# untitled2.net
KiCad netlist of a schematic drawn in EAGLE
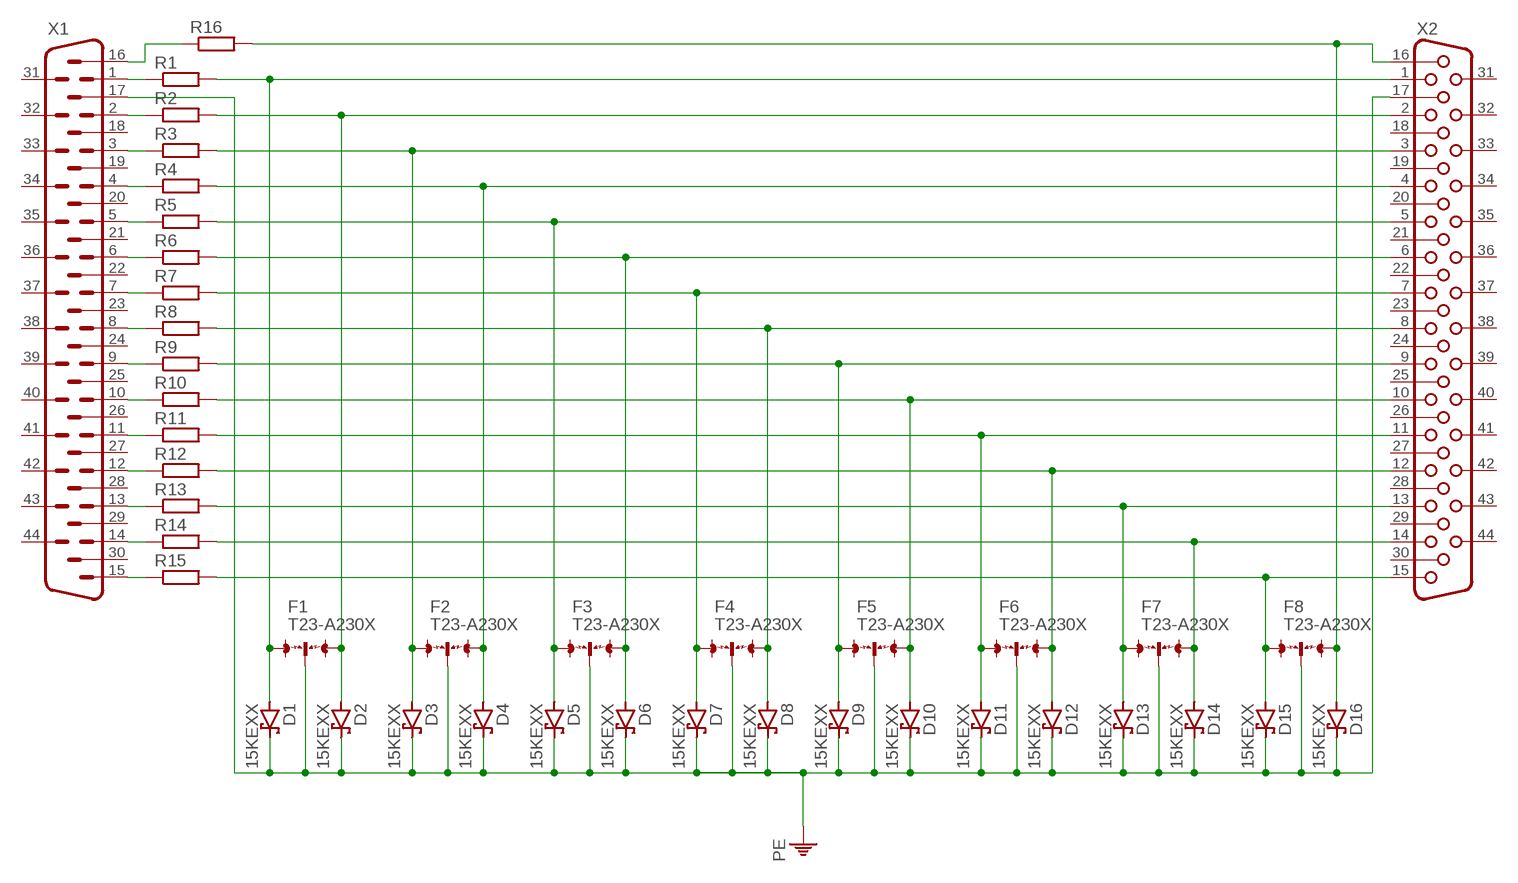
[diagram p0: schematic, sheet 1]

(export (version "E")
  (design (tool "Eeschema 10.0.6"))
  (components
    (comp (ref "D1")
      (value "15KEXX")
      (footprint "eagle-import:CB429-17")
      (libsource (lib "eagle-import") (part "15KEXX"))
    )
    (comp (ref "D2")
      (value "15KEXX")
      (footprint "eagle-import:CB429-17")
      (libsource (lib "eagle-import") (part "15KEXX"))
    )
    (comp (ref "D3")
      (value "15KEXX")
      (footprint "eagle-import:CB429-17")
      (libsource (lib "eagle-import") (part "15KEXX"))
    )
    (comp (ref "D4")
      (value "15KEXX")
      (footprint "eagle-import:CB429-17")
      (libsource (lib "eagle-import") (part "15KEXX"))
    )
    (comp (ref "D5")
      (value "15KEXX")
      (footprint "eagle-import:CB429-17")
      (libsource (lib "eagle-import") (part "15KEXX"))
    )
    (comp (ref "D6")
      (value "15KEXX")
      (footprint "eagle-import:CB429-17")
      (libsource (lib "eagle-import") (part "15KEXX"))
    )
    (comp (ref "D7")
      (value "15KEXX")
      (footprint "eagle-import:CB429-17")
      (libsource (lib "eagle-import") (part "15KEXX"))
    )
    (comp (ref "D8")
      (value "15KEXX")
      (footprint "eagle-import:CB429-17")
      (libsource (lib "eagle-import") (part "15KEXX"))
    )
    (comp (ref "D9")
      (value "15KEXX")
      (footprint "eagle-import:CB429-17")
      (libsource (lib "eagle-import") (part "15KEXX"))
    )
    (comp (ref "D10")
      (value "15KEXX")
      (footprint "eagle-import:CB429-17")
      (libsource (lib "eagle-import") (part "15KEXX"))
    )
    (comp (ref "D11")
      (value "15KEXX")
      (footprint "eagle-import:CB429-17")
      (libsource (lib "eagle-import") (part "15KEXX"))
    )
    (comp (ref "D12")
      (value "15KEXX")
      (footprint "eagle-import:CB429-17")
      (libsource (lib "eagle-import") (part "15KEXX"))
    )
    (comp (ref "D13")
      (value "15KEXX")
      (footprint "eagle-import:CB429-17")
      (libsource (lib "eagle-import") (part "15KEXX"))
    )
    (comp (ref "D14")
      (value "15KEXX")
      (footprint "eagle-import:CB429-17")
      (libsource (lib "eagle-import") (part "15KEXX"))
    )
    (comp (ref "D15")
      (value "15KEXX")
      (footprint "eagle-import:CB429-17")
      (libsource (lib "eagle-import") (part "15KEXX"))
    )
    (comp (ref "D16")
      (value "15KEXX")
      (footprint "eagle-import:CB429-17")
      (libsource (lib "eagle-import") (part "15KEXX"))
    )
    (comp (ref "F1")
      (value "T23-A230X")
      (footprint "eagle-import:T23-A230X")
      (libsource (lib "eagle-import") (part "T23-A230X"))
    )
    (comp (ref "F2")
      (value "T23-A230X")
      (footprint "eagle-import:T23-A230X")
      (libsource (lib "eagle-import") (part "T23-A230X"))
    )
    (comp (ref "F3")
      (value "T23-A230X")
      (footprint "eagle-import:T23-A230X")
      (libsource (lib "eagle-import") (part "T23-A230X"))
    )
    (comp (ref "F4")
      (value "T23-A230X")
      (footprint "eagle-import:T23-A230X")
      (libsource (lib "eagle-import") (part "T23-A230X"))
    )
    (comp (ref "F5")
      (value "T23-A230X")
      (footprint "eagle-import:T23-A230X")
      (libsource (lib "eagle-import") (part "T23-A230X"))
    )
    (comp (ref "F6")
      (value "T23-A230X")
      (footprint "eagle-import:T23-A230X")
      (libsource (lib "eagle-import") (part "T23-A230X"))
    )
    (comp (ref "F7")
      (value "T23-A230X")
      (footprint "eagle-import:T23-A230X")
      (libsource (lib "eagle-import") (part "T23-A230X"))
    )
    (comp (ref "F8")
      (value "T23-A230X")
      (footprint "eagle-import:T23-A230X")
      (libsource (lib "eagle-import") (part "T23-A230X"))
    )
    (comp (ref "R1")
      (value "R-EU_R1210")
      (footprint "eagle-import:R1210")
      (libsource (lib "eagle-import") (part "R-EU_R1210"))
    )
    (comp (ref "R2")
      (value "R-EU_R1210")
      (footprint "eagle-import:R1210")
      (libsource (lib "eagle-import") (part "R-EU_R1210"))
    )
    (comp (ref "R3")
      (value "R-EU_R1210")
      (footprint "eagle-import:R1210")
      (libsource (lib "eagle-import") (part "R-EU_R1210"))
    )
    (comp (ref "R4")
      (value "R-EU_R1210")
      (footprint "eagle-import:R1210")
      (libsource (lib "eagle-import") (part "R-EU_R1210"))
    )
    (comp (ref "R5")
      (value "R-EU_R1210")
      (footprint "eagle-import:R1210")
      (libsource (lib "eagle-import") (part "R-EU_R1210"))
    )
    (comp (ref "R6")
      (value "R-EU_R1210")
      (footprint "eagle-import:R1210")
      (libsource (lib "eagle-import") (part "R-EU_R1210"))
    )
    (comp (ref "R7")
      (value "R-EU_R1210")
      (footprint "eagle-import:R1210")
      (libsource (lib "eagle-import") (part "R-EU_R1210"))
    )
    (comp (ref "R8")
      (value "R-EU_R1210")
      (footprint "eagle-import:R1210")
      (libsource (lib "eagle-import") (part "R-EU_R1210"))
    )
    (comp (ref "R9")
      (value "R-EU_R1210")
      (footprint "eagle-import:R1210")
      (libsource (lib "eagle-import") (part "R-EU_R1210"))
    )
    (comp (ref "R10")
      (value "R-EU_R1210")
      (footprint "eagle-import:R1210")
      (libsource (lib "eagle-import") (part "R-EU_R1210"))
    )
    (comp (ref "R11")
      (value "R-EU_R1210")
      (footprint "eagle-import:R1210")
      (libsource (lib "eagle-import") (part "R-EU_R1210"))
    )
    (comp (ref "R12")
      (value "R-EU_R1210")
      (footprint "eagle-import:R1210")
      (libsource (lib "eagle-import") (part "R-EU_R1210"))
    )
    (comp (ref "R13")
      (value "R-EU_R1210")
      (footprint "eagle-import:R1210")
      (libsource (lib "eagle-import") (part "R-EU_R1210"))
    )
    (comp (ref "R14")
      (value "R-EU_R1210")
      (footprint "eagle-import:R1210")
      (libsource (lib "eagle-import") (part "R-EU_R1210"))
    )
    (comp (ref "R15")
      (value "R-EU_R1210")
      (footprint "eagle-import:R1210")
      (libsource (lib "eagle-import") (part "R-EU_R1210"))
    )
    (comp (ref "R16")
      (value "R-EU_R1210")
      (footprint "eagle-import:R1210")
      (libsource (lib "eagle-import") (part "R-EU_R1210"))
    )
    (comp (ref "X1")
      (value "HM44H")
      (footprint "eagle-import:HDM44H")
      (libsource (lib "eagle-import") (part "HM44H"))
    )
    (comp (ref "X2")
      (value "HF44H")
      (footprint "eagle-import:HDF44H")
      (libsource (lib "eagle-import") (part "HF44H"))
    )
  )
  (nets
    (net (code "1") (name "Net-(D1-PadA)") (class "Default")
      (node (ref "D1") (pin "A") (pinfunction "A_A") (pintype "passive"))
      (node (ref "F1") (pin "1") (pinfunction "1_1") (pintype "passive"))
      (node (ref "R1") (pin "2") (pinfunction "2_2") (pintype "passive"))
      (node (ref "X2") (pin "1") (pinfunction "1_1") (pintype "passive"))
    )
    (net (code "2") (name "Net-(D2-PadA)") (class "Default")
      (node (ref "D2") (pin "A") (pinfunction "A_A") (pintype "passive"))
      (node (ref "F1") (pin "3") (pinfunction "3_3") (pintype "passive"))
      (node (ref "R2") (pin "2") (pinfunction "2_2") (pintype "passive"))
      (node (ref "X2") (pin "2") (pinfunction "2_2") (pintype "passive"))
    )
    (net (code "3") (name "Net-(D3-PadA)") (class "Default")
      (node (ref "D3") (pin "A") (pinfunction "A_A") (pintype "passive"))
      (node (ref "F2") (pin "1") (pinfunction "1_1") (pintype "passive"))
      (node (ref "R3") (pin "2") (pinfunction "2_2") (pintype "passive"))
      (node (ref "X2") (pin "3") (pinfunction "3_3") (pintype "passive"))
    )
    (net (code "4") (name "Net-(D4-PadA)") (class "Default")
      (node (ref "D4") (pin "A") (pinfunction "A_A") (pintype "passive"))
      (node (ref "F2") (pin "3") (pinfunction "3_3") (pintype "passive"))
      (node (ref "R4") (pin "2") (pinfunction "2_2") (pintype "passive"))
      (node (ref "X2") (pin "4") (pinfunction "4_4") (pintype "passive"))
    )
    (net (code "5") (name "Net-(D5-PadA)") (class "Default")
      (node (ref "D5") (pin "A") (pinfunction "A_A") (pintype "passive"))
      (node (ref "F3") (pin "1") (pinfunction "1_1") (pintype "passive"))
      (node (ref "R5") (pin "2") (pinfunction "2_2") (pintype "passive"))
      (node (ref "X2") (pin "5") (pinfunction "5_5") (pintype "passive"))
    )
    (net (code "6") (name "Net-(D6-PadA)") (class "Default")
      (node (ref "D6") (pin "A") (pinfunction "A_A") (pintype "passive"))
      (node (ref "F3") (pin "3") (pinfunction "3_3") (pintype "passive"))
      (node (ref "R6") (pin "2") (pinfunction "2_2") (pintype "passive"))
      (node (ref "X2") (pin "6") (pinfunction "6_6") (pintype "passive"))
    )
    (net (code "7") (name "Net-(D7-PadA)") (class "Default")
      (node (ref "D7") (pin "A") (pinfunction "A_A") (pintype "passive"))
      (node (ref "F4") (pin "1") (pinfunction "1_1") (pintype "passive"))
      (node (ref "R7") (pin "2") (pinfunction "2_2") (pintype "passive"))
      (node (ref "X2") (pin "7") (pinfunction "7_7") (pintype "passive"))
    )
    (net (code "8") (name "Net-(D8-PadA)") (class "Default")
      (node (ref "D8") (pin "A") (pinfunction "A_A") (pintype "passive"))
      (node (ref "F4") (pin "3") (pinfunction "3_3") (pintype "passive"))
      (node (ref "R8") (pin "2") (pinfunction "2_2") (pintype "passive"))
      (node (ref "X2") (pin "8") (pinfunction "8_8") (pintype "passive"))
    )
    (net (code "9") (name "Net-(D9-PadA)") (class "Default")
      (node (ref "D9") (pin "A") (pinfunction "A_A") (pintype "passive"))
      (node (ref "F5") (pin "1") (pinfunction "1_1") (pintype "passive"))
      (node (ref "R9") (pin "2") (pinfunction "2_2") (pintype "passive"))
      (node (ref "X2") (pin "9") (pinfunction "9_9") (pintype "passive"))
    )
    (net (code "10") (name "Net-(D10-PadA)") (class "Default")
      (node (ref "D10") (pin "A") (pinfunction "A_A") (pintype "passive"))
      (node (ref "F5") (pin "3") (pinfunction "3_3") (pintype "passive"))
      (node (ref "R10") (pin "2") (pinfunction "2_2") (pintype "passive"))
      (node (ref "X2") (pin "10") (pinfunction "10_10") (pintype "passive"))
    )
    (net (code "11") (name "Net-(D11-PadA)") (class "Default")
      (node (ref "D11") (pin "A") (pinfunction "A_A") (pintype "passive"))
      (node (ref "F6") (pin "1") (pinfunction "1_1") (pintype "passive"))
      (node (ref "R11") (pin "2") (pinfunction "2_2") (pintype "passive"))
      (node (ref "X2") (pin "11") (pinfunction "11_11") (pintype "passive"))
    )
    (net (code "12") (name "Net-(D12-PadA)") (class "Default")
      (node (ref "D12") (pin "A") (pinfunction "A_A") (pintype "passive"))
      (node (ref "F6") (pin "3") (pinfunction "3_3") (pintype "passive"))
      (node (ref "R12") (pin "2") (pinfunction "2_2") (pintype "passive"))
      (node (ref "X2") (pin "12") (pinfunction "12_12") (pintype "passive"))
    )
    (net (code "13") (name "Net-(D13-PadA)") (class "Default")
      (node (ref "D13") (pin "A") (pinfunction "A_A") (pintype "passive"))
      (node (ref "F7") (pin "1") (pinfunction "1_1") (pintype "passive"))
      (node (ref "R13") (pin "2") (pinfunction "2_2") (pintype "passive"))
      (node (ref "X2") (pin "13") (pinfunction "13_13") (pintype "passive"))
    )
    (net (code "14") (name "Net-(D14-PadA)") (class "Default")
      (node (ref "D14") (pin "A") (pinfunction "A_A") (pintype "passive"))
      (node (ref "F7") (pin "3") (pinfunction "3_3") (pintype "passive"))
      (node (ref "R14") (pin "2") (pinfunction "2_2") (pintype "passive"))
      (node (ref "X2") (pin "14") (pinfunction "14_14") (pintype "passive"))
    )
    (net (code "15") (name "Net-(D15-PadA)") (class "Default")
      (node (ref "D15") (pin "A") (pinfunction "A_A") (pintype "passive"))
      (node (ref "F8") (pin "1") (pinfunction "1_1") (pintype "passive"))
      (node (ref "R15") (pin "2") (pinfunction "2_2") (pintype "passive"))
      (node (ref "X2") (pin "15") (pinfunction "15_15") (pintype "passive"))
    )
    (net (code "16") (name "Net-(D16-PadA)") (class "Default")
      (node (ref "D16") (pin "A") (pinfunction "A_A") (pintype "passive"))
      (node (ref "F8") (pin "3") (pinfunction "3_3") (pintype "passive"))
      (node (ref "R16") (pin "2") (pinfunction "2_2") (pintype "passive"))
      (node (ref "X2") (pin "16") (pinfunction "16_16") (pintype "passive"))
    )
    (net (code "17") (name "Net-(R1-Pad1)") (class "Default")
      (node (ref "R1") (pin "1") (pinfunction "1_1") (pintype "passive"))
      (node (ref "X1") (pin "1") (pinfunction "1_1") (pintype "passive"))
    )
    (net (code "18") (name "Net-(R2-Pad1)") (class "Default")
      (node (ref "R2") (pin "1") (pinfunction "1_1") (pintype "passive"))
      (node (ref "X1") (pin "2") (pinfunction "2_2") (pintype "passive"))
    )
    (net (code "19") (name "Net-(R3-Pad1)") (class "Default")
      (node (ref "R3") (pin "1") (pinfunction "1_1") (pintype "passive"))
      (node (ref "X1") (pin "3") (pinfunction "3_3") (pintype "passive"))
    )
    (net (code "20") (name "Net-(R4-Pad1)") (class "Default")
      (node (ref "R4") (pin "1") (pinfunction "1_1") (pintype "passive"))
      (node (ref "X1") (pin "4") (pinfunction "4_4") (pintype "passive"))
    )
    (net (code "21") (name "Net-(R5-Pad1)") (class "Default")
      (node (ref "R5") (pin "1") (pinfunction "1_1") (pintype "passive"))
      (node (ref "X1") (pin "5") (pinfunction "5_5") (pintype "passive"))
    )
    (net (code "22") (name "Net-(R6-Pad1)") (class "Default")
      (node (ref "R6") (pin "1") (pinfunction "1_1") (pintype "passive"))
      (node (ref "X1") (pin "6") (pinfunction "6_6") (pintype "passive"))
    )
    (net (code "23") (name "Net-(R7-Pad1)") (class "Default")
      (node (ref "R7") (pin "1") (pinfunction "1_1") (pintype "passive"))
      (node (ref "X1") (pin "7") (pinfunction "7_7") (pintype "passive"))
    )
    (net (code "24") (name "Net-(R8-Pad1)") (class "Default")
      (node (ref "R8") (pin "1") (pinfunction "1_1") (pintype "passive"))
      (node (ref "X1") (pin "8") (pinfunction "8_8") (pintype "passive"))
    )
    (net (code "25") (name "Net-(R9-Pad1)") (class "Default")
      (node (ref "R9") (pin "1") (pinfunction "1_1") (pintype "passive"))
      (node (ref "X1") (pin "9") (pinfunction "9_9") (pintype "passive"))
    )
    (net (code "26") (name "Net-(R10-Pad1)") (class "Default")
      (node (ref "R10") (pin "1") (pinfunction "1_1") (pintype "passive"))
      (node (ref "X1") (pin "10") (pinfunction "10_10") (pintype "passive"))
    )
    (net (code "27") (name "Net-(R11-Pad1)") (class "Default")
      (node (ref "R11") (pin "1") (pinfunction "1_1") (pintype "passive"))
      (node (ref "X1") (pin "11") (pinfunction "11_11") (pintype "passive"))
    )
    (net (code "28") (name "Net-(R12-Pad1)") (class "Default")
      (node (ref "R12") (pin "1") (pinfunction "1_1") (pintype "passive"))
      (node (ref "X1") (pin "12") (pinfunction "12_12") (pintype "passive"))
    )
    (net (code "29") (name "Net-(R13-Pad1)") (class "Default")
      (node (ref "R13") (pin "1") (pinfunction "1_1") (pintype "passive"))
      (node (ref "X1") (pin "13") (pinfunction "13_13") (pintype "passive"))
    )
    (net (code "30") (name "Net-(R14-Pad1)") (class "Default")
      (node (ref "R14") (pin "1") (pinfunction "1_1") (pintype "passive"))
      (node (ref "X1") (pin "14") (pinfunction "14_14") (pintype "passive"))
    )
    (net (code "31") (name "Net-(R15-Pad1)") (class "Default")
      (node (ref "R15") (pin "1") (pinfunction "1_1") (pintype "passive"))
      (node (ref "X1") (pin "15") (pinfunction "15_15") (pintype "passive"))
    )
    (net (code "32") (name "Net-(R16-Pad1)") (class "Default")
      (node (ref "R16") (pin "1") (pinfunction "1_1") (pintype "passive"))
      (node (ref "X1") (pin "16") (pinfunction "16_16") (pintype "passive"))
    )
    (net (code "33") (name "PE") (class "Default")
      (node (ref "D1") (pin "C") (pinfunction "C_C") (pintype "passive"))
      (node (ref "D10") (pin "C") (pinfunction "C_C") (pintype "passive"))
      (node (ref "D11") (pin "C") (pinfunction "C_C") (pintype "passive"))
      (node (ref "D12") (pin "C") (pinfunction "C_C") (pintype "passive"))
      (node (ref "D13") (pin "C") (pinfunction "C_C") (pintype "passive"))
      (node (ref "D14") (pin "C") (pinfunction "C_C") (pintype "passive"))
      (node (ref "D15") (pin "C") (pinfunction "C_C") (pintype "passive"))
      (node (ref "D16") (pin "C") (pinfunction "C_C") (pintype "passive"))
      (node (ref "D2") (pin "C") (pinfunction "C_C") (pintype "passive"))
      (node (ref "D3") (pin "C") (pinfunction "C_C") (pintype "passive"))
      (node (ref "D4") (pin "C") (pinfunction "C_C") (pintype "passive"))
      (node (ref "D5") (pin "C") (pinfunction "C_C") (pintype "passive"))
      (node (ref "D6") (pin "C") (pinfunction "C_C") (pintype "passive"))
      (node (ref "D7") (pin "C") (pinfunction "C_C") (pintype "passive"))
      (node (ref "D8") (pin "C") (pinfunction "C_C") (pintype "passive"))
      (node (ref "D9") (pin "C") (pinfunction "C_C") (pintype "passive"))
      (node (ref "F1") (pin "2") (pinfunction "2_2") (pintype "passive"))
      (node (ref "F2") (pin "2") (pinfunction "2_2") (pintype "passive"))
      (node (ref "F3") (pin "2") (pinfunction "2_2") (pintype "passive"))
      (node (ref "F4") (pin "2") (pinfunction "2_2") (pintype "passive"))
      (node (ref "F5") (pin "2") (pinfunction "2_2") (pintype "passive"))
      (node (ref "F6") (pin "2") (pinfunction "2_2") (pintype "passive"))
      (node (ref "F7") (pin "2") (pinfunction "2_2") (pintype "passive"))
      (node (ref "F8") (pin "2") (pinfunction "2_2") (pintype "passive"))
      (node (ref "X1") (pin "17") (pinfunction "17_17") (pintype "passive"))
      (node (ref "X2") (pin "17") (pinfunction "17_17") (pintype "passive"))
    )
    (net (code "34") (name "unconnected-(X1-Pad18)") (class "Default")
      (node (ref "X1") (pin "18") (pinfunction "18_18") (pintype "passive"))
    )
    (net (code "35") (name "unconnected-(X1-Pad19)") (class "Default")
      (node (ref "X1") (pin "19") (pinfunction "19_19") (pintype "passive"))
    )
    (net (code "36") (name "unconnected-(X1-Pad20)") (class "Default")
      (node (ref "X1") (pin "20") (pinfunction "20_20") (pintype "passive"))
    )
    (net (code "37") (name "unconnected-(X1-Pad21)") (class "Default")
      (node (ref "X1") (pin "21") (pinfunction "21_21") (pintype "passive"))
    )
    (net (code "38") (name "unconnected-(X1-Pad22)") (class "Default")
      (node (ref "X1") (pin "22") (pinfunction "22_22") (pintype "passive"))
    )
    (net (code "39") (name "unconnected-(X1-Pad23)") (class "Default")
      (node (ref "X1") (pin "23") (pinfunction "23_23") (pintype "passive"))
    )
    (net (code "40") (name "unconnected-(X1-Pad24)") (class "Default")
      (node (ref "X1") (pin "24") (pinfunction "24_24") (pintype "passive"))
    )
    (net (code "41") (name "unconnected-(X1-Pad25)") (class "Default")
      (node (ref "X1") (pin "25") (pinfunction "25_25") (pintype "passive"))
    )
    (net (code "42") (name "unconnected-(X1-Pad26)") (class "Default")
      (node (ref "X1") (pin "26") (pinfunction "26_26") (pintype "passive"))
    )
    (net (code "43") (name "unconnected-(X1-Pad27)") (class "Default")
      (node (ref "X1") (pin "27") (pinfunction "27_27") (pintype "passive"))
    )
    (net (code "44") (name "unconnected-(X1-Pad28)") (class "Default")
      (node (ref "X1") (pin "28") (pinfunction "28_28") (pintype "passive"))
    )
    (net (code "45") (name "unconnected-(X1-Pad29)") (class "Default")
      (node (ref "X1") (pin "29") (pinfunction "29_29") (pintype "passive"))
    )
    (net (code "46") (name "unconnected-(X1-Pad30)") (class "Default")
      (node (ref "X1") (pin "30") (pinfunction "30_30") (pintype "passive"))
    )
    (net (code "47") (name "unconnected-(X1-Pad31)") (class "Default")
      (node (ref "X1") (pin "31") (pinfunction "31_31") (pintype "passive"))
    )
    (net (code "48") (name "unconnected-(X1-Pad32)") (class "Default")
      (node (ref "X1") (pin "32") (pinfunction "32_32") (pintype "passive"))
    )
    (net (code "49") (name "unconnected-(X1-Pad33)") (class "Default")
      (node (ref "X1") (pin "33") (pinfunction "33_33") (pintype "passive"))
    )
    (net (code "50") (name "unconnected-(X1-Pad34)") (class "Default")
      (node (ref "X1") (pin "34") (pinfunction "34_34") (pintype "passive"))
    )
    (net (code "51") (name "unconnected-(X1-Pad35)") (class "Default")
      (node (ref "X1") (pin "35") (pinfunction "35_35") (pintype "passive"))
    )
    (net (code "52") (name "unconnected-(X1-Pad36)") (class "Default")
      (node (ref "X1") (pin "36") (pinfunction "36_36") (pintype "passive"))
    )
    (net (code "53") (name "unconnected-(X1-Pad37)") (class "Default")
      (node (ref "X1") (pin "37") (pinfunction "37_37") (pintype "passive"))
    )
    (net (code "54") (name "unconnected-(X1-Pad38)") (class "Default")
      (node (ref "X1") (pin "38") (pinfunction "38_38") (pintype "passive"))
    )
    (net (code "55") (name "unconnected-(X1-Pad39)") (class "Default")
      (node (ref "X1") (pin "39") (pinfunction "39_39") (pintype "passive"))
    )
    (net (code "56") (name "unconnected-(X1-Pad40)") (class "Default")
      (node (ref "X1") (pin "40") (pinfunction "40_40") (pintype "passive"))
    )
    (net (code "57") (name "unconnected-(X1-Pad41)") (class "Default")
      (node (ref "X1") (pin "41") (pinfunction "41_41") (pintype "passive"))
    )
    (net (code "58") (name "unconnected-(X1-Pad42)") (class "Default")
      (node (ref "X1") (pin "42") (pinfunction "42_42") (pintype "passive"))
    )
    (net (code "59") (name "unconnected-(X1-Pad43)") (class "Default")
      (node (ref "X1") (pin "43") (pinfunction "43_43") (pintype "passive"))
    )
    (net (code "60") (name "unconnected-(X1-Pad44)") (class "Default")
      (node (ref "X1") (pin "44") (pinfunction "44_44") (pintype "passive"))
    )
    (net (code "61") (name "unconnected-(X2-Pad18)") (class "Default")
      (node (ref "X2") (pin "18") (pinfunction "18_18") (pintype "passive"))
    )
    (net (code "62") (name "unconnected-(X2-Pad19)") (class "Default")
      (node (ref "X2") (pin "19") (pinfunction "19_19") (pintype "passive"))
    )
    (net (code "63") (name "unconnected-(X2-Pad20)") (class "Default")
      (node (ref "X2") (pin "20") (pinfunction "20_20") (pintype "passive"))
    )
    (net (code "64") (name "unconnected-(X2-Pad21)") (class "Default")
      (node (ref "X2") (pin "21") (pinfunction "21_21") (pintype "passive"))
    )
    (net (code "65") (name "unconnected-(X2-Pad22)") (class "Default")
      (node (ref "X2") (pin "22") (pinfunction "22_22") (pintype "passive"))
    )
    (net (code "66") (name "unconnected-(X2-Pad23)") (class "Default")
      (node (ref "X2") (pin "23") (pinfunction "23_23") (pintype "passive"))
    )
    (net (code "67") (name "unconnected-(X2-Pad24)") (class "Default")
      (node (ref "X2") (pin "24") (pinfunction "24_24") (pintype "passive"))
    )
    (net (code "68") (name "unconnected-(X2-Pad25)") (class "Default")
      (node (ref "X2") (pin "25") (pinfunction "25_25") (pintype "passive"))
    )
    (net (code "69") (name "unconnected-(X2-Pad26)") (class "Default")
      (node (ref "X2") (pin "26") (pinfunction "26_26") (pintype "passive"))
    )
    (net (code "70") (name "unconnected-(X2-Pad27)") (class "Default")
      (node (ref "X2") (pin "27") (pinfunction "27_27") (pintype "passive"))
    )
    (net (code "71") (name "unconnected-(X2-Pad28)") (class "Default")
      (node (ref "X2") (pin "28") (pinfunction "28_28") (pintype "passive"))
    )
    (net (code "72") (name "unconnected-(X2-Pad29)") (class "Default")
      (node (ref "X2") (pin "29") (pinfunction "29_29") (pintype "passive"))
    )
    (net (code "73") (name "unconnected-(X2-Pad30)") (class "Default")
      (node (ref "X2") (pin "30") (pinfunction "30_30") (pintype "passive"))
    )
    (net (code "74") (name "unconnected-(X2-Pad31)") (class "Default")
      (node (ref "X2") (pin "31") (pinfunction "31_31") (pintype "passive"))
    )
    (net (code "75") (name "unconnected-(X2-Pad32)") (class "Default")
      (node (ref "X2") (pin "32") (pinfunction "32_32") (pintype "passive"))
    )
    (net (code "76") (name "unconnected-(X2-Pad33)") (class "Default")
      (node (ref "X2") (pin "33") (pinfunction "33_33") (pintype "passive"))
    )
    (net (code "77") (name "unconnected-(X2-Pad34)") (class "Default")
      (node (ref "X2") (pin "34") (pinfunction "34_34") (pintype "passive"))
    )
    (net (code "78") (name "unconnected-(X2-Pad35)") (class "Default")
      (node (ref "X2") (pin "35") (pinfunction "35_35") (pintype "passive"))
    )
    (net (code "79") (name "unconnected-(X2-Pad36)") (class "Default")
      (node (ref "X2") (pin "36") (pinfunction "36_36") (pintype "passive"))
    )
    (net (code "80") (name "unconnected-(X2-Pad37)") (class "Default")
      (node (ref "X2") (pin "37") (pinfunction "37_37") (pintype "passive"))
    )
    (net (code "81") (name "unconnected-(X2-Pad38)") (class "Default")
      (node (ref "X2") (pin "38") (pinfunction "38_38") (pintype "passive"))
    )
    (net (code "82") (name "unconnected-(X2-Pad39)") (class "Default")
      (node (ref "X2") (pin "39") (pinfunction "39_39") (pintype "passive"))
    )
    (net (code "83") (name "unconnected-(X2-Pad40)") (class "Default")
      (node (ref "X2") (pin "40") (pinfunction "40_40") (pintype "passive"))
    )
    (net (code "84") (name "unconnected-(X2-Pad41)") (class "Default")
      (node (ref "X2") (pin "41") (pinfunction "41_41") (pintype "passive"))
    )
    (net (code "85") (name "unconnected-(X2-Pad42)") (class "Default")
      (node (ref "X2") (pin "42") (pinfunction "42_42") (pintype "passive"))
    )
    (net (code "86") (name "unconnected-(X2-Pad43)") (class "Default")
      (node (ref "X2") (pin "43") (pinfunction "43_43") (pintype "passive"))
    )
    (net (code "87") (name "unconnected-(X2-Pad44)") (class "Default")
      (node (ref "X2") (pin "44") (pinfunction "44_44") (pintype "passive"))
    )
  )
)
